# Rev4.net
KiCad netlist of a schematic drawn in EAGLE
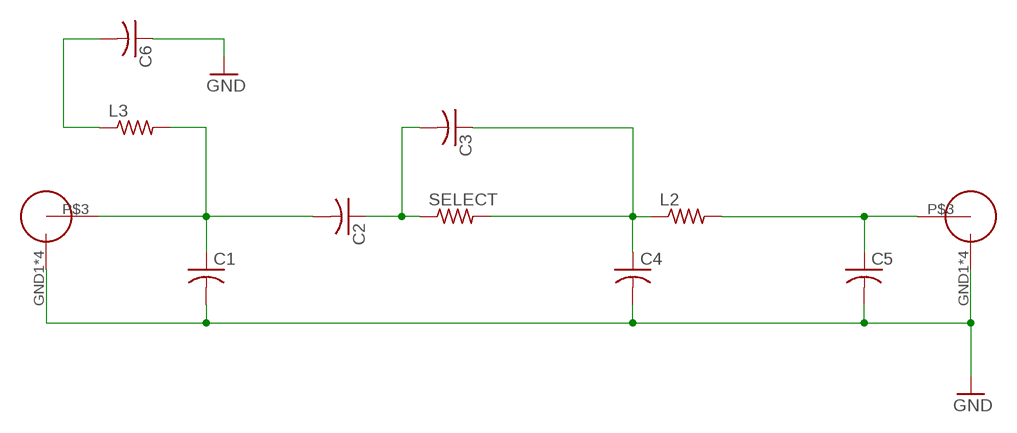
[diagram p0: schematic, sheet 1]

(export (version "E")
  (design (tool "Eeschema 10.0.6"))
  (components
    (comp (ref "C1")
      (value "C-USC0603")
      (footprint "eagle-import:C0603")
      (libsource (lib "eagle-import") (part "C-USC0603"))
    )
    (comp (ref "C2")
      (value "C-USC0603")
      (footprint "eagle-import:C0603")
      (libsource (lib "eagle-import") (part "C-USC0603"))
    )
    (comp (ref "C3")
      (value "C-USC0603")
      (footprint "eagle-import:C0603")
      (libsource (lib "eagle-import") (part "C-USC0603"))
    )
    (comp (ref "C4")
      (value "C-USC0603")
      (footprint "eagle-import:C0603")
      (libsource (lib "eagle-import") (part "C-USC0603"))
    )
    (comp (ref "C5")
      (value "C-USC0603")
      (footprint "eagle-import:C0603")
      (libsource (lib "eagle-import") (part "C-USC0603"))
    )
    (comp (ref "C6")
      (value "C-USC0603")
      (footprint "eagle-import:C0603")
      (libsource (lib "eagle-import") (part "C-USC0603"))
    )
    (comp (ref "L2")
      (value "R-US_R0603")
      (footprint "eagle-import:R0603")
      (libsource (lib "eagle-import") (part "R-US_R0603"))
    )
    (comp (ref "L3")
      (value "R-US_R0603")
      (footprint "eagle-import:R0603")
      (libsource (lib "eagle-import") (part "R-US_R0603"))
    )
    (comp (ref "SELECT")
      (value "R-US_R0603")
      (footprint "eagle-import:R0603")
      (libsource (lib "eagle-import") (part "R-US_R0603"))
    )
    (comp (ref "U$1")
      (value "SMAJ716-ND")
      (footprint "eagle-import:SMAJ716-ND")
      (libsource (lib "eagle-import") (part "SMAJ716-ND"))
    )
    (comp (ref "U$2")
      (value "SMAJ716-ND")
      (footprint "eagle-import:SMAJ716-ND")
      (libsource (lib "eagle-import") (part "SMAJ716-ND"))
    )
  )
  (nets
    (net (code "1") (name "GND") (class "Default")
      (node (ref "C1") (pin "2") (pinfunction "2_2") (pintype "passive"))
      (node (ref "C4") (pin "2") (pinfunction "2_2") (pintype "passive"))
      (node (ref "C5") (pin "2") (pinfunction "2_2") (pintype "passive"))
      (node (ref "C6") (pin "1") (pinfunction "1_1") (pintype "passive"))
      (node (ref "U$1") (pin "GND1") (pinfunction "OUTERCONDUCTOR_GND1") (pintype "bidirectional"))
      (node (ref "U$1") (pin "GND2") (pinfunction "OUTERCONDUCTOR_GND2") (pintype "bidirectional"))
      (node (ref "U$1") (pin "GND3") (pinfunction "OUTERCONDUCTOR_GND3") (pintype "bidirectional"))
      (node (ref "U$1") (pin "GND4") (pinfunction "OUTERCONDUCTOR_GND4") (pintype "bidirectional"))
      (node (ref "U$2") (pin "GND1") (pinfunction "OUTERCONDUCTOR_GND1") (pintype "bidirectional"))
      (node (ref "U$2") (pin "GND2") (pinfunction "OUTERCONDUCTOR_GND2") (pintype "bidirectional"))
      (node (ref "U$2") (pin "GND3") (pinfunction "OUTERCONDUCTOR_GND3") (pintype "bidirectional"))
      (node (ref "U$2") (pin "GND4") (pinfunction "OUTERCONDUCTOR_GND4") (pintype "bidirectional"))
    )
    (net (code "2") (name "Net-(C2-Pad1)") (class "Default")
      (node (ref "C2") (pin "1") (pinfunction "1_1") (pintype "passive"))
      (node (ref "C3") (pin "2") (pinfunction "2_2") (pintype "passive"))
      (node (ref "SELECT") (pin "1") (pinfunction "1_1") (pintype "passive"))
    )
    (net (code "3") (name "Net-(C3-Pad1)") (class "Default")
      (node (ref "C3") (pin "1") (pinfunction "1_1") (pintype "passive"))
      (node (ref "C4") (pin "1") (pinfunction "1_1") (pintype "passive"))
      (node (ref "L2") (pin "1") (pinfunction "1_1") (pintype "passive"))
      (node (ref "SELECT") (pin "2") (pinfunction "2_2") (pintype "passive"))
    )
    (net (code "4") (name "Net-(C6-Pad2)") (class "Default")
      (node (ref "C6") (pin "2") (pinfunction "2_2") (pintype "passive"))
      (node (ref "L3") (pin "1") (pinfunction "1_1") (pintype "passive"))
    )
    (net (code "5") (name "Net-(U$1-CENTERCONDUCTOR)") (class "Default")
      (node (ref "C1") (pin "1") (pinfunction "1_1") (pintype "passive"))
      (node (ref "C2") (pin "2") (pinfunction "2_2") (pintype "passive"))
      (node (ref "L3") (pin "2") (pinfunction "2_2") (pintype "passive"))
      (node (ref "U$1") (pin "P$3") (pinfunction "CENTERCONDUCTOR_P$3") (pintype "bidirectional"))
    )
    (net (code "6") (name "Net-(U$2-CENTERCONDUCTOR)") (class "Default")
      (node (ref "C5") (pin "1") (pinfunction "1_1") (pintype "passive"))
      (node (ref "L2") (pin "2") (pinfunction "2_2") (pintype "passive"))
      (node (ref "U$2") (pin "P$3") (pinfunction "CENTERCONDUCTOR_P$3") (pintype "bidirectional"))
    )
  )
)
